# ul_rx.net
KiCad netlist of a schematic drawn in Altium Designer
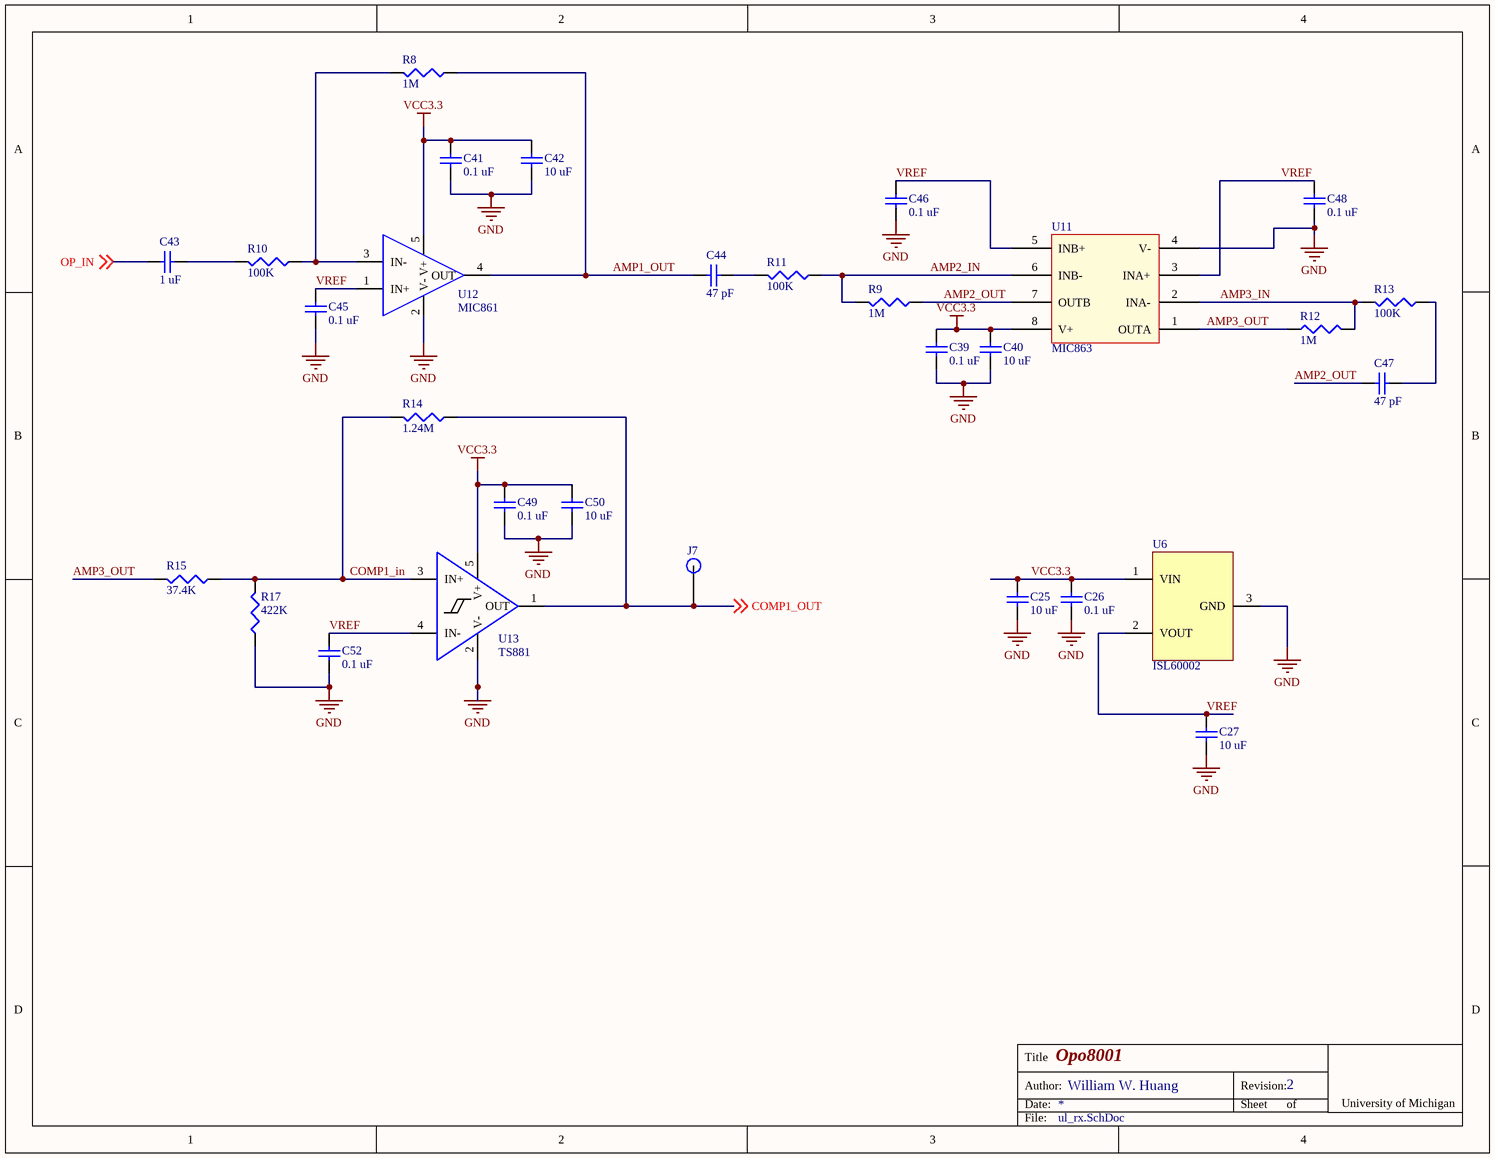
[diagram p0: ul_rx.SchDoc]

(export (version "E")
  (design (tool "Eeschema 10.0.6"))
  (components
    (comp (ref "C25")
      (value "10 uF")
      (footprint "0603")
      (description "Ceramic capacitor, 10 uF, 0603 package")
      (fields (field (name "TOLERANCE") "20%") (field (name "Comment") "Ceramic capacitor"))
      (libsource (lib "rlc") (part "C_10u_0603_ceramic"))
    )
    (comp (ref "C26")
      (value "0.1 uF")
      (footprint "0402")
      (description "Ceramic capacitor, 0.1u, 0402 package")
      (fields (field (name "TOLERANCE") "10%") (field (name "Comment") "Ceramic capacitor"))
      (libsource (lib "rlc") (part "C_0.1u_0402_ceramic"))
    )
    (comp (ref "C27")
      (value "10 uF")
      (footprint "0603")
      (description "Ceramic capacitor, 10 uF, 0603 package")
      (fields (field (name "TOLERANCE") "20%") (field (name "Comment") "Ceramic capacitor"))
      (libsource (lib "rlc") (part "C_10u_0603_ceramic"))
    )
    (comp (ref "C39")
      (value "0.1 uF")
      (footprint "0402")
      (description "Ceramic capacitor, 0.1u, 0402 package")
      (fields (field (name "TOLERANCE") "10%") (field (name "Comment") "Ceramic capacitor"))
      (libsource (lib "rlc") (part "C_0.1u_0402_ceramic"))
    )
    (comp (ref "C40")
      (value "10 uF")
      (footprint "0402")
      (description "Ceramic capacitor, 10 uF, 0402 package")
      (fields (field (name "TOLERANCE") "20%") (field (name "Comment") "Ceramic capacitor"))
      (libsource (lib "rlc") (part "C_10u_0402_ceramic"))
    )
    (comp (ref "C41")
      (value "0.1 uF")
      (footprint "0402")
      (description "Ceramic capacitor, 0.1u, 0402 package")
      (fields (field (name "TOLERANCE") "10%") (field (name "Comment") "Ceramic capacitor"))
      (libsource (lib "rlc") (part "C_0.1u_0402_ceramic"))
    )
    (comp (ref "C42")
      (value "10 uF")
      (footprint "0402")
      (description "Ceramic capacitor, 10 uF, 0402 package")
      (fields (field (name "TOLERANCE") "20%") (field (name "Comment") "Ceramic capacitor"))
      (libsource (lib "rlc") (part "C_10u_0402_ceramic"))
    )
    (comp (ref "C43")
      (value "1 uF")
      (footprint "0402")
      (description "Ceramic capacitor, 1 uF, 0402 package")
      (fields (field (name "TOLERANCE") "10%") (field (name "Comment") "Ceramic capacitor"))
      (libsource (lib "rlc") (part "C_1u_0402_ceramic"))
    )
    (comp (ref "C44")
      (value "47 pF")
      (footprint "0402")
      (description "Ceramic capacitor, 47 pF, 0402 package")
      (fields (field (name "TOLERANCE") "5%") (field (name "Comment") "Ceramic capacitor"))
      (libsource (lib "rlc") (part "C_47p_0402_ceramic"))
    )
    (comp (ref "C45")
      (value "0.1 uF")
      (footprint "0402")
      (description "Ceramic capacitor, 0.1u, 0402 package")
      (fields (field (name "TOLERANCE") "10%") (field (name "Comment") "Ceramic capacitor"))
      (libsource (lib "rlc") (part "C_0.1u_0402_ceramic"))
    )
    (comp (ref "C46")
      (value "0.1 uF")
      (footprint "0402")
      (description "Ceramic capacitor, 0.1u, 0402 package")
      (fields (field (name "TOLERANCE") "10%") (field (name "Comment") "Ceramic capacitor"))
      (libsource (lib "rlc") (part "C_0.1u_0402_ceramic"))
    )
    (comp (ref "C47")
      (value "47 pF")
      (footprint "0402")
      (description "Ceramic capacitor, 47 pF, 0402 package")
      (fields (field (name "TOLERANCE") "5%") (field (name "Comment") "Ceramic capacitor"))
      (libsource (lib "rlc") (part "C_47p_0402_ceramic"))
    )
    (comp (ref "C48")
      (value "0.1 uF")
      (footprint "0402")
      (description "Ceramic capacitor, 0.1u, 0402 package")
      (fields (field (name "TOLERANCE") "10%") (field (name "Comment") "Ceramic capacitor"))
      (libsource (lib "rlc") (part "C_0.1u_0402_ceramic"))
    )
    (comp (ref "C49")
      (value "0.1 uF")
      (footprint "0402")
      (description "Ceramic capacitor, 0.1u, 0402 package")
      (fields (field (name "TOLERANCE") "10%") (field (name "Comment") "Ceramic capacitor"))
      (libsource (lib "rlc") (part "C_0.1u_0402_ceramic"))
    )
    (comp (ref "C50")
      (value "10 uF")
      (footprint "0402")
      (description "Ceramic capacitor, 10 uF, 0402 package")
      (fields (field (name "TOLERANCE") "20%") (field (name "Comment") "Ceramic capacitor"))
      (libsource (lib "rlc") (part "C_10u_0402_ceramic"))
    )
    (comp (ref "C52")
      (value "0.1 uF")
      (footprint "0402")
      (description "Ceramic capacitor, 0.1u, 0402 package")
      (fields (field (name "TOLERANCE") "10%") (field (name "Comment") "Ceramic capacitor"))
      (libsource (lib "rlc") (part "C_0.1u_0402_ceramic"))
    )
    (comp (ref "J7")
      (value "RCU 0603 SMD Testpoint")
      (footprint "RCU_0603")
      (description "0603 SMD Testpoint")
      (libsource (lib "connectors") (part "Testpoint-0603"))
    )
    (comp (ref "R8")
      (value "1M")
      (footprint "0402")
      (description "Chip resistor, 1M, 0402 package")
      (fields (field (name "TOLERANCE") "1%") (field (name "POWER") "1/16 W"))
      (libsource (lib "rlc") (part "R_1M_0402"))
    )
    (comp (ref "R9")
      (value "1M")
      (footprint "0402")
      (description "Chip resistor, 1M, 0402 package")
      (fields (field (name "TOLERANCE") "1%") (field (name "POWER") "1/16 W"))
      (libsource (lib "rlc") (part "R_1M_0402"))
    )
    (comp (ref "R10")
      (value "100K")
      (footprint "0402")
      (description "Chip resistor, 100K, 0402 package")
      (fields (field (name "TOLERANCE") "1%") (field (name "POWER") "1/16 W"))
      (libsource (lib "rlc") (part "R_100K_0402"))
    )
    (comp (ref "R11")
      (value "100K")
      (footprint "0402")
      (description "Chip resistor, 100K, 0402 package")
      (fields (field (name "TOLERANCE") "1%") (field (name "POWER") "1/16 W"))
      (libsource (lib "rlc") (part "R_100K_0402"))
    )
    (comp (ref "R12")
      (value "1M")
      (footprint "0402")
      (description "Chip resistor, 1M, 0402 package")
      (fields (field (name "TOLERANCE") "1%") (field (name "POWER") "1/16 W"))
      (libsource (lib "rlc") (part "R_1M_0402"))
    )
    (comp (ref "R13")
      (value "100K")
      (footprint "0402")
      (description "Chip resistor, 100K, 0402 package")
      (fields (field (name "TOLERANCE") "1%") (field (name "POWER") "1/16 W"))
      (libsource (lib "rlc") (part "R_100K_0402"))
    )
    (comp (ref "R14")
      (value "1.24M")
      (footprint "0402")
      (description "Chip resistor, 1.24M, 0402 package")
      (fields (field (name "TOLERANCE") "1%") (field (name "POWER") "1/16 W"))
      (libsource (lib "rlc") (part "R_1.24M_0402"))
    )
    (comp (ref "R15")
      (value "37.4K")
      (footprint "0402")
      (description "Chip resistor, 37.4K, 0402 package")
      (fields (field (name "TOLERANCE") "1%") (field (name "POWER") "1/16 W"))
      (libsource (lib "rlc") (part "R_37.4K_0402"))
    )
    (comp (ref "R17")
      (value "422K")
      (footprint "0402")
      (description "Chip resistor, 422K, 0402 package")
      (fields (field (name "TOLERANCE") "1%") (field (name "POWER") "1/16 W"))
      (libsource (lib "rlc") (part "R_422K_0402"))
    )
    (comp (ref "U6")
      (value "ISL60002")
      (footprint "SOT23-3N")
      (description "IC VREF SERIES PREC SOT-23-3")
      (libsource (lib "opo") (part "ISL60002"))
    )
    (comp (ref "U11")
      (value "MIC863")
      (footprint "TSOP65P280X145-8N")
      (description "Dual Ultra Low Power Op Amp in SOT23-8")
      (libsource (lib "opo_general") (part "MIC863"))
    )
    (comp (ref "U12")
      (value "MIC861")
      (footprint "SC70-5")
      (description "IC OPAMP 400KHZ 2.7V ULT LP SC70")
      (libsource (lib "opo_general") (part "MIC861"))
    )
    (comp (ref "U13")
      (value "TS881")
      (footprint "SC70-5")
      (description "Rail-to-rail 1.1 V nanopower comparator")
      (libsource (lib "opo_general") (part "TS881"))
    )
  )
  (nets
    (net (code "1") (name "/AMP1_OUT") (class "Default")
      (node (ref "C44") (pin "1") (pintype "passive"))
      (node (ref "R8") (pin "2") (pintype "passive"))
      (node (ref "U12") (pin "4") (pinfunction "OUT_4") (pintype "passive"))
    )
    (net (code "2") (name "/AMP2_IN") (class "Default")
      (node (ref "R11") (pin "2") (pintype "passive"))
      (node (ref "R9") (pin "1") (pintype "passive"))
      (node (ref "U11") (pin "6") (pinfunction "INB-_6") (pintype "passive"))
    )
    (net (code "3") (name "/AMP2_OUT") (class "Default")
      (node (ref "C47") (pin "1") (pintype "passive"))
      (node (ref "R9") (pin "2") (pintype "passive"))
      (node (ref "U11") (pin "7") (pinfunction "OUTB_7") (pintype "passive"))
    )
    (net (code "4") (name "/AMP3_IN") (class "Default")
      (node (ref "R12") (pin "1") (pintype "passive"))
      (node (ref "R13") (pin "1") (pintype "passive"))
      (node (ref "U11") (pin "2") (pinfunction "INA-_2") (pintype "passive"))
    )
    (net (code "5") (name "/AMP3_OUT") (class "Default")
      (node (ref "R12") (pin "2") (pintype "passive"))
      (node (ref "R15") (pin "1") (pintype "passive"))
      (node (ref "U11") (pin "1") (pinfunction "OUTA_1") (pintype "passive"))
    )
    (net (code "6") (name "/COMP1_in") (class "Default")
      (node (ref "R14") (pin "1") (pintype "passive"))
      (node (ref "R15") (pin "2") (pintype "passive"))
      (node (ref "R17") (pin "1") (pintype "passive"))
      (node (ref "U13") (pin "3") (pinfunction "IN+_3") (pintype "passive"))
    )
    (net (code "7") (name "/VREF") (class "Default")
      (node (ref "C27") (pin "1") (pintype "passive"))
      (node (ref "C45") (pin "1") (pintype "passive"))
      (node (ref "C46") (pin "1") (pintype "passive"))
      (node (ref "C48") (pin "1") (pintype "passive"))
      (node (ref "C52") (pin "1") (pintype "passive"))
      (node (ref "U11") (pin "3") (pinfunction "INA+_3") (pintype "passive"))
      (node (ref "U11") (pin "5") (pinfunction "INB+_5") (pintype "passive"))
      (node (ref "U12") (pin "1") (pinfunction "IN+_1") (pintype "passive"))
      (node (ref "U13") (pin "4") (pinfunction "IN-_4") (pintype "passive"))
      (node (ref "U6") (pin "2") (pinfunction "VOUT_2") (pintype "passive"))
    )
    (net (code "8") (name "COMP1_OUT") (class "Default")
      (node (ref "J7") (pin "1") (pinfunction "J_1") (pintype "passive"))
      (node (ref "R14") (pin "2") (pintype "passive"))
      (node (ref "U13") (pin "1") (pinfunction "OUT_1") (pintype "passive"))
    )
    (net (code "9") (name "GND") (class "Default")
      (node (ref "C25") (pin "2") (pintype "passive"))
      (node (ref "C26") (pin "2") (pintype "passive"))
      (node (ref "C27") (pin "2") (pintype "passive"))
      (node (ref "C39") (pin "2") (pintype "passive"))
      (node (ref "C40") (pin "2") (pintype "passive"))
      (node (ref "C41") (pin "2") (pintype "passive"))
      (node (ref "C42") (pin "2") (pintype "passive"))
      (node (ref "C45") (pin "2") (pintype "passive"))
      (node (ref "C46") (pin "2") (pintype "passive"))
      (node (ref "C48") (pin "2") (pintype "passive"))
      (node (ref "C49") (pin "2") (pintype "passive"))
      (node (ref "C50") (pin "2") (pintype "passive"))
      (node (ref "C52") (pin "2") (pintype "passive"))
      (node (ref "R17") (pin "2") (pintype "passive"))
      (node (ref "U11") (pin "4") (pinfunction "V-_4") (pintype "passive"))
      (node (ref "U12") (pin "2") (pinfunction "V-_2") (pintype "passive"))
      (node (ref "U13") (pin "2") (pinfunction "V-_2") (pintype "passive"))
      (node (ref "U6") (pin "3") (pinfunction "GND_3") (pintype "passive"))
    )
    (net (code "10") (name "Net-(C43-Pad2)") (class "Default")
      (node (ref "C43") (pin "2") (pintype "passive"))
      (node (ref "R10") (pin "1") (pintype "passive"))
    )
    (net (code "11") (name "Net-(C44-Pad2)") (class "Default")
      (node (ref "C44") (pin "2") (pintype "passive"))
      (node (ref "R11") (pin "1") (pintype "passive"))
    )
    (net (code "12") (name "Net-(C47-Pad2)") (class "Default")
      (node (ref "C47") (pin "2") (pintype "passive"))
      (node (ref "R13") (pin "2") (pintype "passive"))
    )
    (net (code "13") (name "Net-(U12-IN-)") (class "Default")
      (node (ref "R10") (pin "2") (pintype "passive"))
      (node (ref "R8") (pin "1") (pintype "passive"))
      (node (ref "U12") (pin "3") (pinfunction "IN-_3") (pintype "passive"))
    )
    (net (code "14") (name "OP_IN") (class "Default") (node (ref "C43") (pin "1") (pintype "passive")))
    (net (code "15") (name "VCC3.3") (class "Default")
      (node (ref "C25") (pin "1") (pintype "passive"))
      (node (ref "C26") (pin "1") (pintype "passive"))
      (node (ref "C39") (pin "1") (pintype "passive"))
      (node (ref "C40") (pin "1") (pintype "passive"))
      (node (ref "C41") (pin "1") (pintype "passive"))
      (node (ref "C42") (pin "1") (pintype "passive"))
      (node (ref "C49") (pin "1") (pintype "passive"))
      (node (ref "C50") (pin "1") (pintype "passive"))
      (node (ref "U11") (pin "8") (pinfunction "V+_8") (pintype "passive"))
      (node (ref "U12") (pin "5") (pinfunction "V+_5") (pintype "passive"))
      (node (ref "U13") (pin "5") (pinfunction "V+_5") (pintype "passive"))
      (node (ref "U6") (pin "1") (pinfunction "VIN_1") (pintype "passive"))
    )
  )
)
